# TouchWidget_HowTo.net
KiCad netlist of a schematic drawn in EAGLE
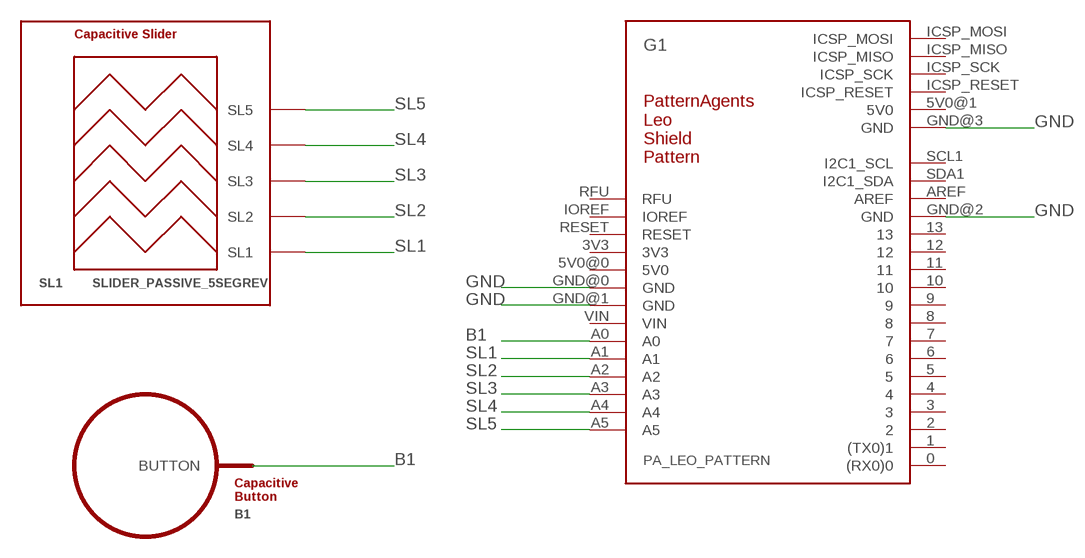
[diagram p0: schematic, sheet 1]

(export (version "E")
  (design (tool "Eeschema 10.0.6"))
  (components
    (comp (ref "B1")
      (value "BUTTON_PASSIVE10MM")
      (footprint "eagle-import:BUTTON_PASSIVE_10MM")
      (libsource (lib "eagle-import") (part "BUTTON_PASSIVE10MM"))
    )
    (comp (ref "G1")
      (value "PA_LEO_PATTERN")
      (footprint "eagle-import:PA_LEO_PATTERN")
      (libsource (lib "eagle-import") (part "PA_LEO_PATTERN"))
    )
    (comp (ref "SL1")
      (value "SLIDER_PASSIVE_5SEGREV")
      (footprint "eagle-import:SLIDER_PASSIVE_5SEG_12MM_REV")
      (libsource (lib "eagle-import") (part "SLIDER_PASSIVE_5SEGREV"))
    )
  )
  (nets
    (net (code "1") (name "/5V0") (class "Default")
      (node (ref "G1") (pin "5V0@1") (pinfunction "5V0_5V0@1") (pintype "power_in"))
    )
    (net (code "2") (name "/B1") (class "Default")
      (node (ref "B1") (pin "BUTTON") (pinfunction "BUTTON_BUTTON") (pintype "passive"))
      (node (ref "G1") (pin "A0") (pinfunction "A0_A0") (pintype "bidirectional"))
    )
    (net (code "3") (name "/GND") (class "Default")
      (node (ref "G1") (pin "GND@0") (pinfunction "GND_GND@0") (pintype "bidirectional"))
      (node (ref "G1") (pin "GND@1") (pinfunction "GND_GND@1") (pintype "bidirectional"))
      (node (ref "G1") (pin "GND@2") (pinfunction "GND_GND@2") (pintype "bidirectional"))
      (node (ref "G1") (pin "GND@3") (pinfunction "GND_GND@3") (pintype "power_in"))
    )
    (net (code "4") (name "/RFU") (class "Default")
      (node (ref "G1") (pin "RFU") (pinfunction "RFU_RFU") (pintype "power_in"))
    )
    (net (code "5") (name "/SL1") (class "Default")
      (node (ref "G1") (pin "A1") (pinfunction "A1_A1") (pintype "bidirectional"))
      (node (ref "SL1") (pin "SL1") (pinfunction "SL1_SL1") (pintype "passive"))
    )
    (net (code "6") (name "/SL2") (class "Default")
      (node (ref "G1") (pin "A2") (pinfunction "A2_A2") (pintype "bidirectional"))
      (node (ref "SL1") (pin "SL2") (pinfunction "SL2_SL2") (pintype "passive"))
    )
    (net (code "7") (name "/SL3") (class "Default")
      (node (ref "G1") (pin "A3") (pinfunction "A3_A3") (pintype "bidirectional"))
      (node (ref "SL1") (pin "SL3") (pinfunction "SL3_SL3") (pintype "passive"))
    )
    (net (code "8") (name "/SL4") (class "Default")
      (node (ref "G1") (pin "A4") (pinfunction "A4_A4") (pintype "bidirectional"))
      (node (ref "SL1") (pin "SL4") (pinfunction "SL4_SL4") (pintype "passive"))
    )
    (net (code "9") (name "/SL5") (class "Default")
      (node (ref "G1") (pin "A5") (pinfunction "A5_A5") (pintype "bidirectional"))
      (node (ref "SL1") (pin "SL5") (pinfunction "SL5_SL5") (pintype "passive"))
    )
    (net (code "10") (name "unconnected-(G1-(RX0)0-Pad0)") (class "Default")
      (node (ref "G1") (pin "0") (pinfunction "(RX0)0_0") (pintype "bidirectional"))
    )
    (net (code "11") (name "unconnected-(G1-(TX0)1-Pad1)") (class "Default")
      (node (ref "G1") (pin "1") (pinfunction "(TX0)1_1") (pintype "bidirectional"))
    )
    (net (code "12") (name "unconnected-(G1-5V0-Pad5V0@0)") (class "Default")
      (node (ref "G1") (pin "5V0@0") (pinfunction "5V0_5V0@0") (pintype "bidirectional"))
    )
    (net (code "13") (name "unconnected-(G1-I2C1_SCL-PadSCL1)") (class "Default")
      (node (ref "G1") (pin "SCL1") (pinfunction "I2C1_SCL_SCL1") (pintype "bidirectional"))
    )
    (net (code "14") (name "unconnected-(G1-I2C1_SDA-PadSDA1)") (class "Default")
      (node (ref "G1") (pin "SDA1") (pinfunction "I2C1_SDA_SDA1") (pintype "bidirectional"))
    )
    (net (code "15") (name "unconnected-(G1-Pad2)") (class "Default")
      (node (ref "G1") (pin "2") (pinfunction "2_2") (pintype "bidirectional"))
    )
    (net (code "16") (name "unconnected-(G1-Pad3)") (class "Default")
      (node (ref "G1") (pin "3") (pinfunction "3_3") (pintype "bidirectional"))
    )
    (net (code "17") (name "unconnected-(G1-Pad3V3)") (class "Default")
      (node (ref "G1") (pin "3V3") (pinfunction "3V3_3V3") (pintype "bidirectional"))
    )
    (net (code "18") (name "unconnected-(G1-Pad4)") (class "Default")
      (node (ref "G1") (pin "4") (pinfunction "4_4") (pintype "bidirectional"))
    )
    (net (code "19") (name "unconnected-(G1-Pad5)") (class "Default")
      (node (ref "G1") (pin "5") (pinfunction "5_5") (pintype "bidirectional"))
    )
    (net (code "20") (name "unconnected-(G1-Pad6)") (class "Default")
      (node (ref "G1") (pin "6") (pinfunction "6_6") (pintype "bidirectional"))
    )
    (net (code "21") (name "unconnected-(G1-Pad7)") (class "Default")
      (node (ref "G1") (pin "7") (pinfunction "7_7") (pintype "bidirectional"))
    )
    (net (code "22") (name "unconnected-(G1-Pad8)") (class "Default")
      (node (ref "G1") (pin "8") (pinfunction "8_8") (pintype "bidirectional"))
    )
    (net (code "23") (name "unconnected-(G1-Pad9)") (class "Default")
      (node (ref "G1") (pin "9") (pinfunction "9_9") (pintype "bidirectional"))
    )
    (net (code "24") (name "unconnected-(G1-Pad10)") (class "Default")
      (node (ref "G1") (pin "10") (pinfunction "10_10") (pintype "bidirectional"))
    )
    (net (code "25") (name "unconnected-(G1-Pad11)") (class "Default")
      (node (ref "G1") (pin "11") (pinfunction "11_11") (pintype "bidirectional"))
    )
    (net (code "26") (name "unconnected-(G1-Pad12)") (class "Default")
      (node (ref "G1") (pin "12") (pinfunction "12_12") (pintype "bidirectional"))
    )
    (net (code "27") (name "unconnected-(G1-Pad13)") (class "Default")
      (node (ref "G1") (pin "13") (pinfunction "13_13") (pintype "bidirectional"))
    )
    (net (code "28") (name "unconnected-(G1-PadAREF)") (class "Default")
      (node (ref "G1") (pin "AREF") (pinfunction "AREF_AREF") (pintype "bidirectional"))
    )
    (net (code "29") (name "unconnected-(G1-PadICSP_MISO)") (class "Default")
      (node (ref "G1") (pin "ICSP_MISO") (pinfunction "ICSP_MISO_ICSP_MISO") (pintype "bidirectional"))
    )
    (net (code "30") (name "unconnected-(G1-PadICSP_MOSI)") (class "Default")
      (node (ref "G1") (pin "ICSP_MOSI") (pinfunction "ICSP_MOSI_ICSP_MOSI") (pintype "bidirectional"))
    )
    (net (code "31") (name "unconnected-(G1-PadICSP_RESET)") (class "Default")
      (node (ref "G1") (pin "ICSP_RESET") (pinfunction "ICSP_RESET_ICSP_RESET") (pintype "bidirectional"))
    )
    (net (code "32") (name "unconnected-(G1-PadICSP_SCK)") (class "Default")
      (node (ref "G1") (pin "ICSP_SCK") (pinfunction "ICSP_SCK_ICSP_SCK") (pintype "bidirectional"))
    )
    (net (code "33") (name "unconnected-(G1-PadIOREF)") (class "Default")
      (node (ref "G1") (pin "IOREF") (pinfunction "IOREF_IOREF") (pintype "output"))
    )
    (net (code "34") (name "unconnected-(G1-PadRESET)") (class "Default")
      (node (ref "G1") (pin "RESET") (pinfunction "RESET_RESET") (pintype "bidirectional"))
    )
    (net (code "35") (name "unconnected-(G1-PadVIN)") (class "Default")
      (node (ref "G1") (pin "VIN") (pinfunction "VIN_VIN") (pintype "bidirectional"))
    )
  )
)
